# LuvaAcel.net
KiCad netlist of a schematic drawn in EAGLE
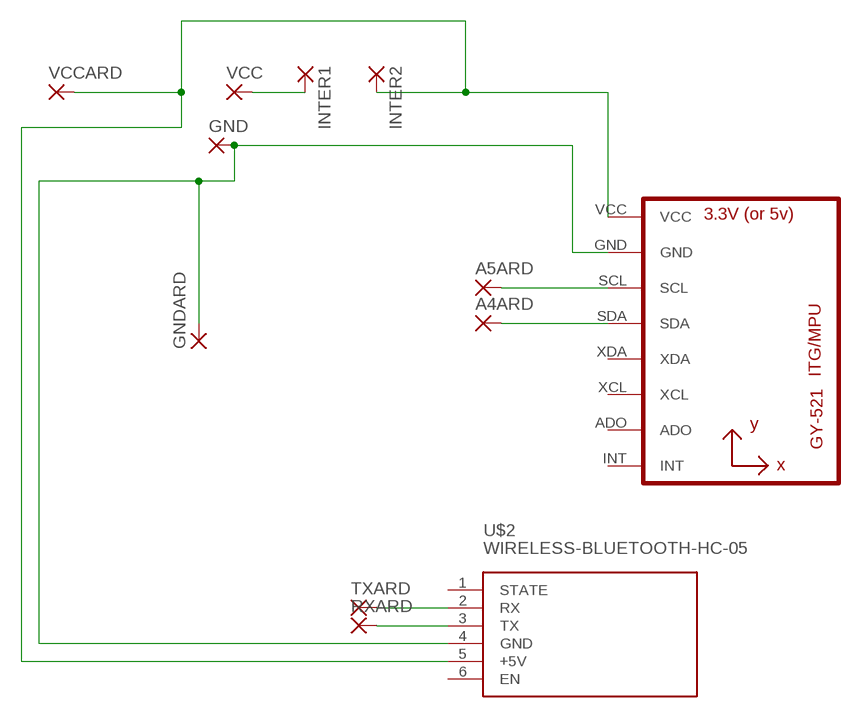
[diagram p0: schematic, sheet 1]

(export (version "E")
  (design (tool "Eeschema 10.0.6"))
  (components
    (comp (ref "A4ARD")
      (value "3,17/1,1")
      (footprint "eagle-import:3,17_1,1")
      (libsource (lib "eagle-import") (part "3,17/1,1"))
    )
    (comp (ref "A5ARD")
      (value "3,17/1,1")
      (footprint "eagle-import:3,17_1,1")
      (libsource (lib "eagle-import") (part "3,17/1,1"))
    )
    (comp (ref "GND")
      (value "3,17/1,1")
      (footprint "eagle-import:3,17_1,1")
      (libsource (lib "eagle-import") (part "3,17/1,1"))
    )
    (comp (ref "GNDARD")
      (value "3,17/1,1")
      (footprint "eagle-import:3,17_1,1")
      (libsource (lib "eagle-import") (part "3,17/1,1"))
    )
    (comp (ref "INTER1")
      (value "3,17/1,1")
      (footprint "eagle-import:3,17_1,1")
      (libsource (lib "eagle-import") (part "3,17/1,1"))
    )
    (comp (ref "INTER2")
      (value "3,17/1,1")
      (footprint "eagle-import:3,17_1,1")
      (libsource (lib "eagle-import") (part "3,17/1,1"))
    )
    (comp (ref "RXARD")
      (value "3,17/1,1")
      (footprint "eagle-import:3,17_1,1")
      (libsource (lib "eagle-import") (part "3,17/1,1"))
    )
    (comp (ref "TXARD")
      (value "3,17/1,1")
      (footprint "eagle-import:3,17_1,1")
      (libsource (lib "eagle-import") (part "3,17/1,1"))
    )
    (comp (ref "U$2")
      (value "WIRELESS-BLUETOOTH-HC-05")
      (footprint "eagle-import:WIRELESS-BLUETOOTH-HC-05")
      (libsource (lib "eagle-import") (part "WIRELESS-BLUETOOTH-HC-05"))
    )
    (comp (ref "U1")
      (value "GY-521MPU6050")
      (footprint "eagle-import:GY-521")
      (libsource (lib "eagle-import") (part "GY-521MPU6050"))
    )
    (comp (ref "VCC")
      (value "3,17/1,1")
      (footprint "eagle-import:3,17_1,1")
      (libsource (lib "eagle-import") (part "3,17/1,1"))
    )
    (comp (ref "VCCARD")
      (value "3,17/1,1")
      (footprint "eagle-import:3,17_1,1")
      (libsource (lib "eagle-import") (part "3,17/1,1"))
    )
  )
  (nets
    (net (code "1") (name "Net-(A4ARD-P)") (class "Default")
      (node (ref "A4ARD") (pin "1") (pinfunction "P_1") (pintype "passive"))
      (node (ref "U1") (pin "SDA") (pinfunction "SDA_SDA") (pintype "bidirectional"))
    )
    (net (code "2") (name "Net-(A5ARD-P)") (class "Default")
      (node (ref "A5ARD") (pin "1") (pinfunction "P_1") (pintype "passive"))
      (node (ref "U1") (pin "SCL") (pinfunction "SCL_SCL") (pintype "bidirectional"))
    )
    (net (code "3") (name "Net-(GND-P)") (class "Default")
      (node (ref "GND") (pin "1") (pinfunction "P_1") (pintype "passive"))
      (node (ref "GNDARD") (pin "1") (pinfunction "P_1") (pintype "passive"))
      (node (ref "U$2") (pin "4") (pinfunction "GND_4") (pintype "power_in"))
      (node (ref "U1") (pin "GND") (pinfunction "GND_GND") (pintype "bidirectional"))
    )
    (net (code "4") (name "Net-(INTER1-P)") (class "Default")
      (node (ref "INTER1") (pin "1") (pinfunction "P_1") (pintype "passive"))
      (node (ref "VCC") (pin "1") (pinfunction "P_1") (pintype "passive"))
    )
    (net (code "5") (name "Net-(INTER2-P)") (class "Default")
      (node (ref "INTER2") (pin "1") (pinfunction "P_1") (pintype "passive"))
      (node (ref "U$2") (pin "5") (pinfunction "+5V_5") (pintype "power_in"))
      (node (ref "U1") (pin "VCC") (pinfunction "VCC_VCC") (pintype "bidirectional"))
      (node (ref "VCCARD") (pin "1") (pinfunction "P_1") (pintype "passive"))
    )
    (net (code "6") (name "Net-(RXARD-P)") (class "Default")
      (node (ref "RXARD") (pin "1") (pinfunction "P_1") (pintype "passive"))
      (node (ref "U$2") (pin "3") (pinfunction "TX_3") (pintype "bidirectional"))
    )
    (net (code "7") (name "Net-(TXARD-P)") (class "Default")
      (node (ref "TXARD") (pin "1") (pinfunction "P_1") (pintype "passive"))
      (node (ref "U$2") (pin "2") (pinfunction "RX_2") (pintype "bidirectional"))
    )
    (net (code "8") (name "unconnected-(U$2-EN-Pad6)") (class "Default")
      (node (ref "U$2") (pin "6") (pinfunction "EN_6") (pintype "bidirectional"))
    )
    (net (code "9") (name "unconnected-(U$2-STATE-Pad1)") (class "Default")
      (node (ref "U$2") (pin "1") (pinfunction "STATE_1") (pintype "bidirectional"))
    )
    (net (code "10") (name "unconnected-(U1-PadADO)") (class "Default")
      (node (ref "U1") (pin "ADO") (pinfunction "ADO_ADO") (pintype "bidirectional"))
    )
    (net (code "11") (name "unconnected-(U1-PadINT)") (class "Default")
      (node (ref "U1") (pin "INT") (pinfunction "INT_INT") (pintype "bidirectional"))
    )
    (net (code "12") (name "unconnected-(U1-PadXCL)") (class "Default")
      (node (ref "U1") (pin "XCL") (pinfunction "XCL_XCL") (pintype "bidirectional"))
    )
    (net (code "13") (name "unconnected-(U1-PadXDA)") (class "Default")
      (node (ref "U1") (pin "XDA") (pinfunction "XDA_XDA") (pintype "bidirectional"))
    )
  )
)
